# PCB_3U_BNC.net
KiCad netlist of a schematic drawn in Altium Designer
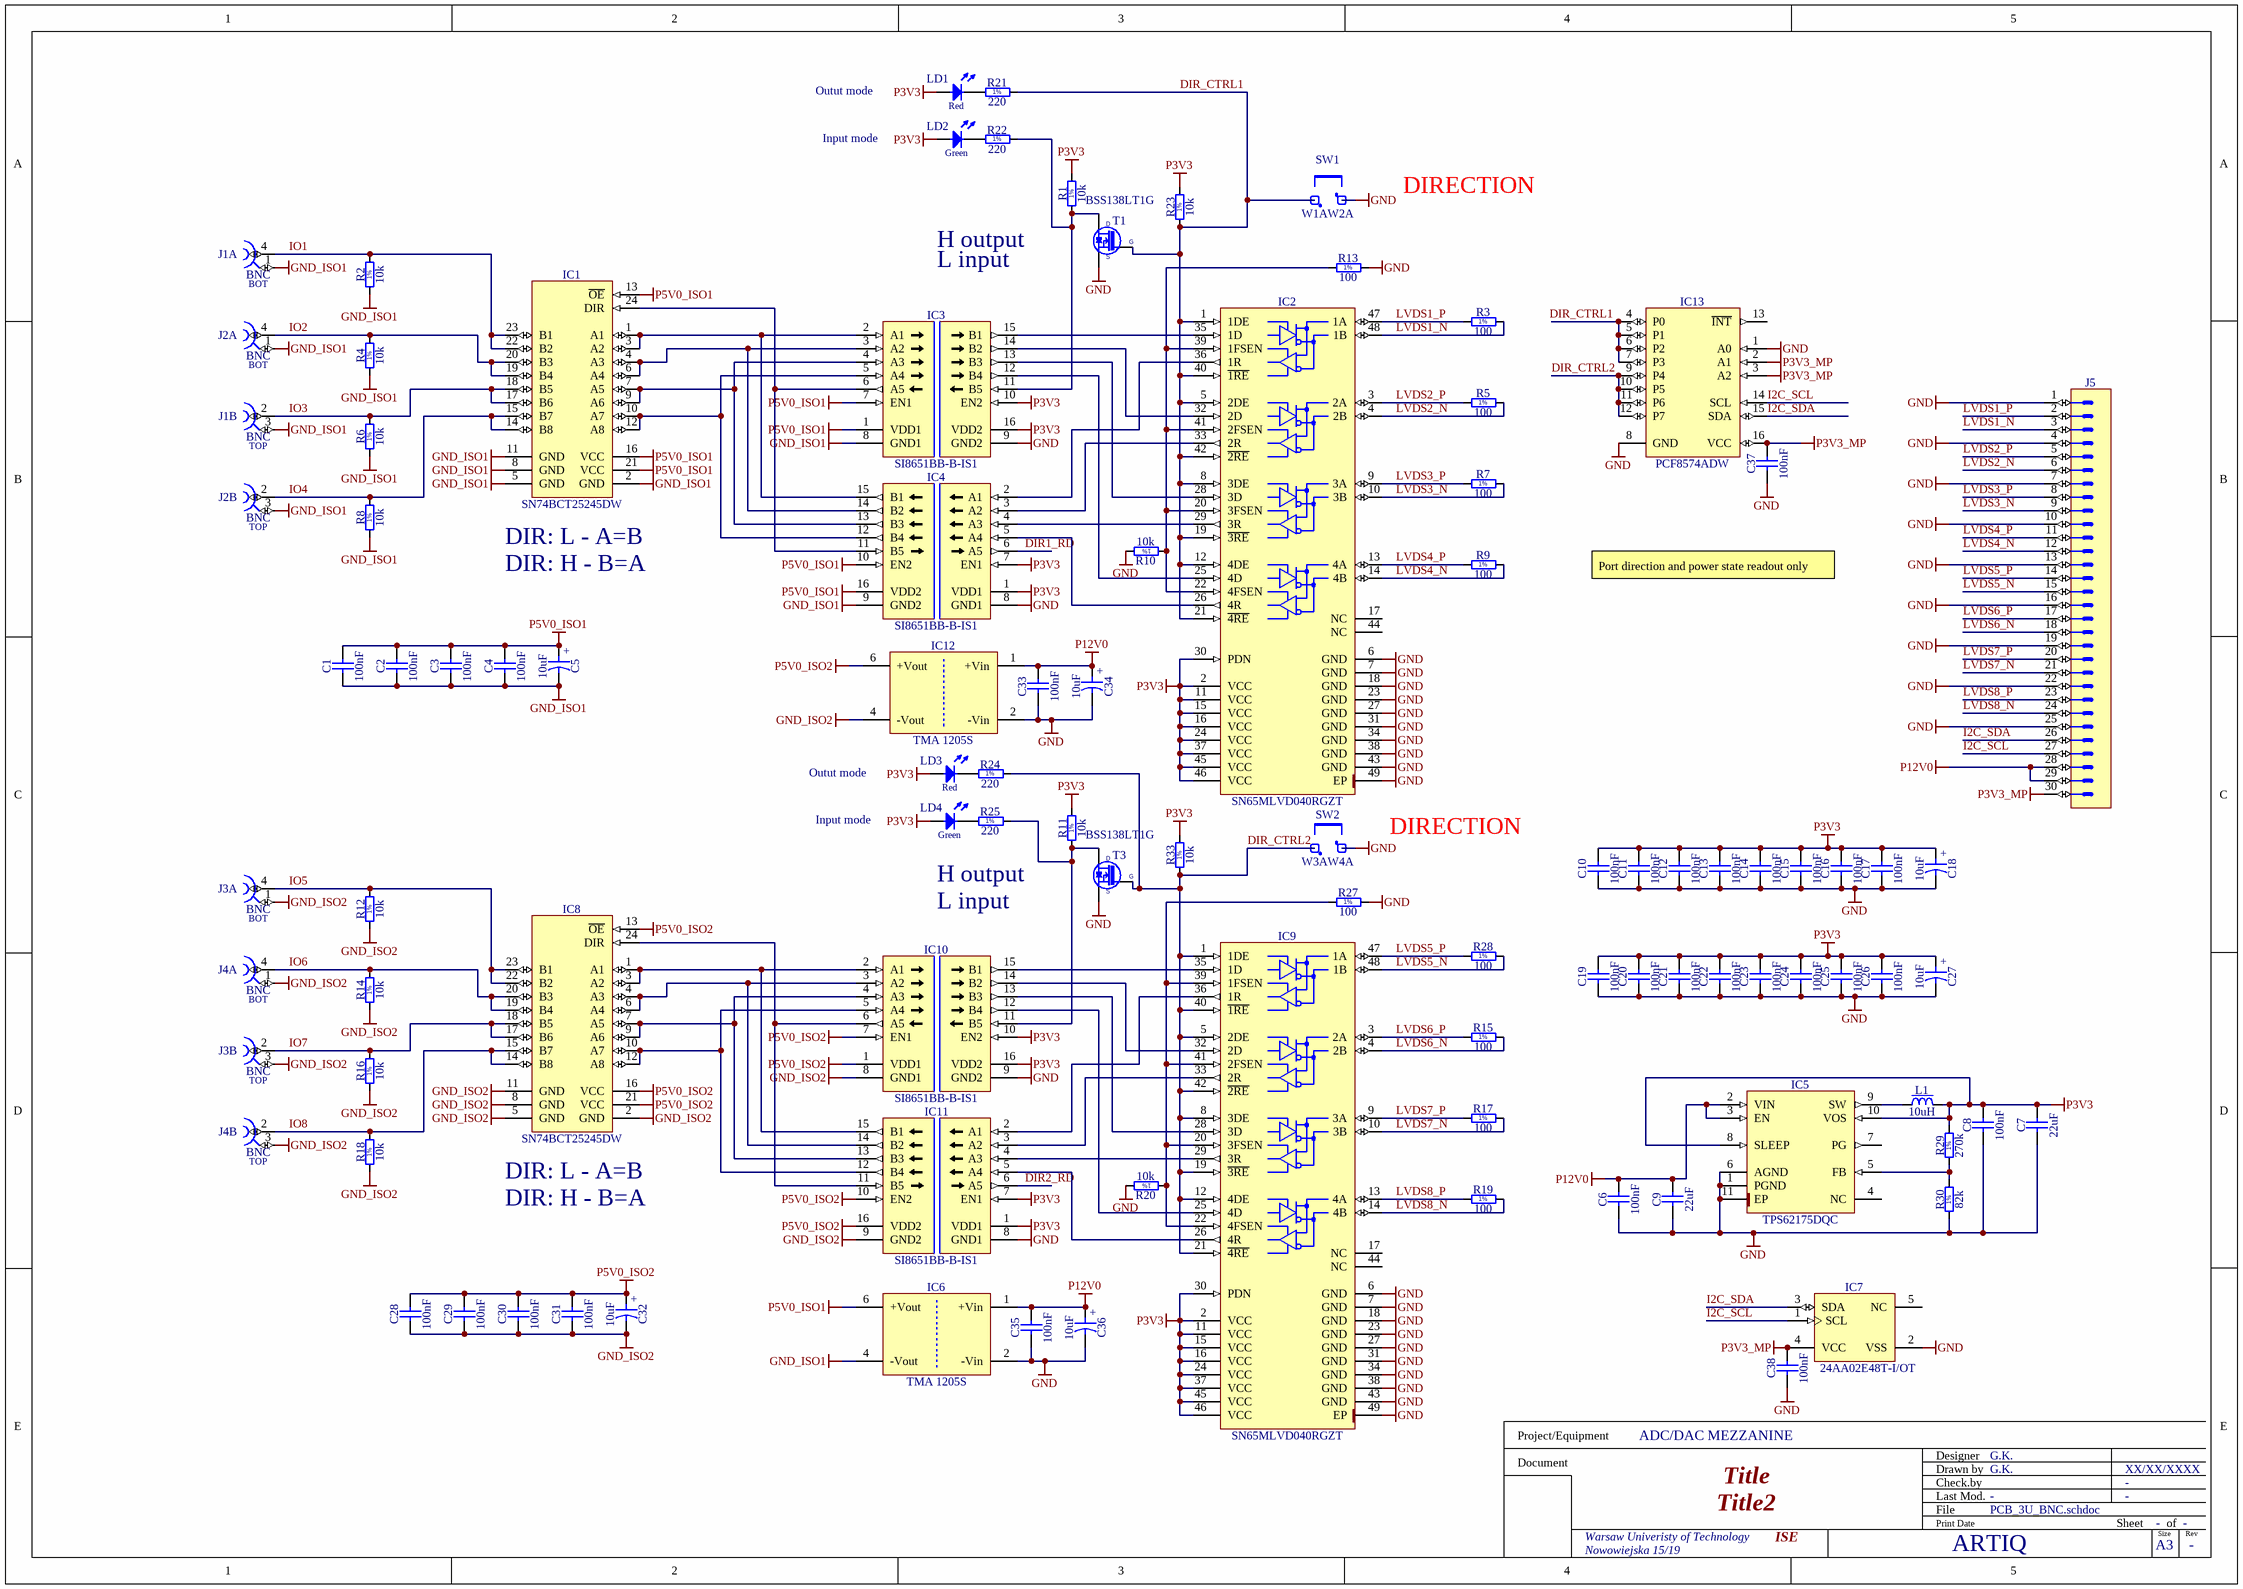
[diagram p0: PCB_3U_BNC.schdoc]

(export (version "E")
  (design (tool "Eeschema 10.0.6"))
  (components
    (comp (ref "C1")
      (value "100nF")
      (footprint "CAPC1005X55N")
      (description "Non-polarised capacitor")
      (fields
        (field (name "PART NUMBER") "CC0402_100NF_16V_10%_X5R")
        (field (name "VOLTAGE") "16V")
        (field (name "AUTHOR") "CERN DEM JLC")
      )
      (libsource (lib "Capacitors") (part "Capacitor - non polarized"))
    )
    (comp (ref "C2")
      (value "100nF")
      (footprint "CAPC1005X55N")
      (description "Non-polarised capacitor")
      (fields
        (field (name "PART NUMBER") "CC0402_100NF_16V_10%_X5R")
        (field (name "VOLTAGE") "16V")
        (field (name "AUTHOR") "CERN DEM JLC")
      )
      (libsource (lib "Capacitors") (part "Capacitor - non polarized"))
    )
    (comp (ref "C3")
      (value "100nF")
      (footprint "CAPC1005X55N")
      (description "Non-polarised capacitor")
      (fields
        (field (name "PART NUMBER") "CC0402_100NF_16V_10%_X5R")
        (field (name "VOLTAGE") "16V")
        (field (name "AUTHOR") "CERN DEM JLC")
      )
      (libsource (lib "Capacitors") (part "Capacitor - non polarized"))
    )
    (comp (ref "C4")
      (value "100nF")
      (footprint "CAPC1005X55N")
      (description "Non-polarised capacitor")
      (fields
        (field (name "PART NUMBER") "CC0402_100NF_16V_10%_X5R")
        (field (name "VOLTAGE") "16V")
        (field (name "AUTHOR") "CERN DEM JLC")
      )
      (libsource (lib "Capacitors") (part "Capacitor - non polarized"))
    )
    (comp (ref "C5")
      (value "10uF")
      (footprint "CAPAE430X540N")
      (description "Polarised capacitor")
      (fields
        (field (name "PART NUMBER") "CAE430-540_10UF_16V_20%")
        (field (name "VOLTAGE") "16V")
        (field (name "AUTHOR") "CERN DEM JLC")
      )
      (libsource (lib "Capacitors") (part "Capacitor - polarized"))
    )
    (comp (ref "C6")
      (value "100nF")
      (footprint "CAPC1005X55N")
      (description "Non-polarised capacitor")
      (fields
        (field (name "PART NUMBER") "CC0402_100NF_16V_10%_X5R")
        (field (name "VOLTAGE") "16V")
        (field (name "AUTHOR") "CERN DEM JLC")
      )
      (libsource (lib "Capacitors") (part "Capacitor - non polarized"))
    )
    (comp (ref "C7")
      (value "22uF")
      (footprint "CAPC2012X135N")
      (description "Non-polarised capacitor")
      (fields
        (field (name "PART NUMBER") "CC0805_22UF_16V_10%_X5R")
        (field (name "VOLTAGE") "16V")
        (field (name "AUTHOR") "CERN DEM JLC")
      )
      (libsource (lib "Capacitors") (part "Capacitor - non polarized"))
    )
    (comp (ref "C8")
      (value "100nF")
      (footprint "CAPC1005X55N")
      (description "Non-polarised capacitor")
      (fields
        (field (name "PART NUMBER") "CC0402_100NF_16V_10%_X5R")
        (field (name "VOLTAGE") "16V")
        (field (name "AUTHOR") "CERN DEM JLC")
      )
      (libsource (lib "Capacitors") (part "Capacitor - non polarized"))
    )
    (comp (ref "C9")
      (value "22uF")
      (footprint "CAPC2012X135N")
      (description "Non-polarised capacitor")
      (fields
        (field (name "PART NUMBER") "CC0805_22UF_16V_10%_X5R")
        (field (name "VOLTAGE") "16V")
        (field (name "AUTHOR") "CERN DEM JLC")
      )
      (libsource (lib "Capacitors") (part "Capacitor - non polarized"))
    )
    (comp (ref "C10")
      (value "100nF")
      (footprint "CAPC1005X55N")
      (description "Non-polarised capacitor")
      (fields
        (field (name "PART NUMBER") "CC0402_100NF_16V_10%_X5R")
        (field (name "VOLTAGE") "16V")
        (field (name "AUTHOR") "CERN DEM JLC")
      )
      (libsource (lib "Capacitors") (part "Capacitor - non polarized"))
    )
    (comp (ref "C11")
      (value "100nF")
      (footprint "CAPC1005X55N")
      (description "Non-polarised capacitor")
      (fields
        (field (name "PART NUMBER") "CC0402_100NF_16V_10%_X5R")
        (field (name "VOLTAGE") "16V")
        (field (name "AUTHOR") "CERN DEM JLC")
      )
      (libsource (lib "Capacitors") (part "Capacitor - non polarized"))
    )
    (comp (ref "C12")
      (value "100nF")
      (footprint "CAPC1005X55N")
      (description "Non-polarised capacitor")
      (fields
        (field (name "PART NUMBER") "CC0402_100NF_16V_10%_X5R")
        (field (name "VOLTAGE") "16V")
        (field (name "AUTHOR") "CERN DEM JLC")
      )
      (libsource (lib "Capacitors") (part "Capacitor - non polarized"))
    )
    (comp (ref "C13")
      (value "100nF")
      (footprint "CAPC1005X55N")
      (description "Non-polarised capacitor")
      (fields
        (field (name "PART NUMBER") "CC0402_100NF_16V_10%_X5R")
        (field (name "VOLTAGE") "16V")
        (field (name "AUTHOR") "CERN DEM JLC")
      )
      (libsource (lib "Capacitors") (part "Capacitor - non polarized"))
    )
    (comp (ref "C14")
      (value "100nF")
      (footprint "CAPC1005X55N")
      (description "Non-polarised capacitor")
      (fields
        (field (name "PART NUMBER") "CC0402_100NF_16V_10%_X5R")
        (field (name "VOLTAGE") "16V")
        (field (name "AUTHOR") "CERN DEM JLC")
      )
      (libsource (lib "Capacitors") (part "Capacitor - non polarized"))
    )
    (comp (ref "C15")
      (value "100nF")
      (footprint "CAPC1005X55N")
      (description "Non-polarised capacitor")
      (fields
        (field (name "PART NUMBER") "CC0402_100NF_16V_10%_X5R")
        (field (name "VOLTAGE") "16V")
        (field (name "AUTHOR") "CERN DEM JLC")
      )
      (libsource (lib "Capacitors") (part "Capacitor - non polarized"))
    )
    (comp (ref "C16")
      (value "100nF")
      (footprint "CAPC1005X55N")
      (description "Non-polarised capacitor")
      (fields
        (field (name "PART NUMBER") "CC0402_100NF_16V_10%_X5R")
        (field (name "VOLTAGE") "16V")
        (field (name "AUTHOR") "CERN DEM JLC")
      )
      (libsource (lib "Capacitors") (part "Capacitor - non polarized"))
    )
    (comp (ref "C17")
      (value "100nF")
      (footprint "CAPC1005X55N")
      (description "Non-polarised capacitor")
      (fields
        (field (name "PART NUMBER") "CC0402_100NF_16V_10%_X5R")
        (field (name "VOLTAGE") "16V")
        (field (name "AUTHOR") "CERN DEM JLC")
      )
      (libsource (lib "Capacitors") (part "Capacitor - non polarized"))
    )
    (comp (ref "C18")
      (value "10uF")
      (footprint "CAPAE430X540N")
      (description "Polarised capacitor")
      (fields
        (field (name "PART NUMBER") "CAE430-540_10UF_16V_20%")
        (field (name "VOLTAGE") "16V")
        (field (name "AUTHOR") "CERN DEM JLC")
      )
      (libsource (lib "Capacitors") (part "Capacitor - polarized"))
    )
    (comp (ref "C19")
      (value "100nF")
      (footprint "CAPC1005X55N")
      (description "Non-polarised capacitor")
      (fields
        (field (name "PART NUMBER") "CC0402_100NF_16V_10%_X5R")
        (field (name "VOLTAGE") "16V")
        (field (name "AUTHOR") "CERN DEM JLC")
      )
      (libsource (lib "Capacitors") (part "Capacitor - non polarized"))
    )
    (comp (ref "C20")
      (value "100nF")
      (footprint "CAPC1005X55N")
      (description "Non-polarised capacitor")
      (fields
        (field (name "PART NUMBER") "CC0402_100NF_16V_10%_X5R")
        (field (name "VOLTAGE") "16V")
        (field (name "AUTHOR") "CERN DEM JLC")
      )
      (libsource (lib "Capacitors") (part "Capacitor - non polarized"))
    )
    (comp (ref "C21")
      (value "100nF")
      (footprint "CAPC1005X55N")
      (description "Non-polarised capacitor")
      (fields
        (field (name "PART NUMBER") "CC0402_100NF_16V_10%_X5R")
        (field (name "VOLTAGE") "16V")
        (field (name "AUTHOR") "CERN DEM JLC")
      )
      (libsource (lib "Capacitors") (part "Capacitor - non polarized"))
    )
    (comp (ref "C22")
      (value "100nF")
      (footprint "CAPC1005X55N")
      (description "Non-polarised capacitor")
      (fields
        (field (name "PART NUMBER") "CC0402_100NF_16V_10%_X5R")
        (field (name "VOLTAGE") "16V")
        (field (name "AUTHOR") "CERN DEM JLC")
      )
      (libsource (lib "Capacitors") (part "Capacitor - non polarized"))
    )
    (comp (ref "C23")
      (value "100nF")
      (footprint "CAPC1005X55N")
      (description "Non-polarised capacitor")
      (fields
        (field (name "PART NUMBER") "CC0402_100NF_16V_10%_X5R")
        (field (name "VOLTAGE") "16V")
        (field (name "AUTHOR") "CERN DEM JLC")
      )
      (libsource (lib "Capacitors") (part "Capacitor - non polarized"))
    )
    (comp (ref "C24")
      (value "100nF")
      (footprint "CAPC1005X55N")
      (description "Non-polarised capacitor")
      (fields
        (field (name "PART NUMBER") "CC0402_100NF_16V_10%_X5R")
        (field (name "VOLTAGE") "16V")
        (field (name "AUTHOR") "CERN DEM JLC")
      )
      (libsource (lib "Capacitors") (part "Capacitor - non polarized"))
    )
    (comp (ref "C25")
      (value "100nF")
      (footprint "CAPC1005X55N")
      (description "Non-polarised capacitor")
      (fields
        (field (name "PART NUMBER") "CC0402_100NF_16V_10%_X5R")
        (field (name "VOLTAGE") "16V")
        (field (name "AUTHOR") "CERN DEM JLC")
      )
      (libsource (lib "Capacitors") (part "Capacitor - non polarized"))
    )
    (comp (ref "C26")
      (value "100nF")
      (footprint "CAPC1005X55N")
      (description "Non-polarised capacitor")
      (fields
        (field (name "PART NUMBER") "CC0402_100NF_16V_10%_X5R")
        (field (name "VOLTAGE") "16V")
        (field (name "AUTHOR") "CERN DEM JLC")
      )
      (libsource (lib "Capacitors") (part "Capacitor - non polarized"))
    )
    (comp (ref "C27")
      (value "10uF")
      (footprint "CAPAE430X540N")
      (description "Polarised capacitor")
      (fields
        (field (name "PART NUMBER") "CAE430-540_10UF_16V_20%")
        (field (name "VOLTAGE") "16V")
        (field (name "AUTHOR") "CERN DEM JLC")
      )
      (libsource (lib "Capacitors") (part "Capacitor - polarized"))
    )
    (comp (ref "C28")
      (value "100nF")
      (footprint "CAPC1005X55N")
      (description "Non-polarised capacitor")
      (fields
        (field (name "PART NUMBER") "CC0402_100NF_16V_10%_X5R")
        (field (name "VOLTAGE") "16V")
        (field (name "AUTHOR") "CERN DEM JLC")
      )
      (libsource (lib "Capacitors") (part "Capacitor - non polarized"))
    )
    (comp (ref "C29")
      (value "100nF")
      (footprint "CAPC1005X55N")
      (description "Non-polarised capacitor")
      (fields
        (field (name "PART NUMBER") "CC0402_100NF_16V_10%_X5R")
        (field (name "VOLTAGE") "16V")
        (field (name "AUTHOR") "CERN DEM JLC")
      )
      (libsource (lib "Capacitors") (part "Capacitor - non polarized"))
    )
    (comp (ref "C30")
      (value "100nF")
      (footprint "CAPC1005X55N")
      (description "Non-polarised capacitor")
      (fields
        (field (name "PART NUMBER") "CC0402_100NF_16V_10%_X5R")
        (field (name "VOLTAGE") "16V")
        (field (name "AUTHOR") "CERN DEM JLC")
      )
      (libsource (lib "Capacitors") (part "Capacitor - non polarized"))
    )
    (comp (ref "C31")
      (value "100nF")
      (footprint "CAPC1005X55N")
      (description "Non-polarised capacitor")
      (fields
        (field (name "PART NUMBER") "CC0402_100NF_16V_10%_X5R")
        (field (name "VOLTAGE") "16V")
        (field (name "AUTHOR") "CERN DEM JLC")
      )
      (libsource (lib "Capacitors") (part "Capacitor - non polarized"))
    )
    (comp (ref "C32")
      (value "10uF")
      (footprint "CAPAE430X540N")
      (description "Polarised capacitor")
      (fields
        (field (name "PART NUMBER") "CAE430-540_10UF_16V_20%")
        (field (name "VOLTAGE") "16V")
        (field (name "AUTHOR") "CERN DEM JLC")
      )
      (libsource (lib "Capacitors") (part "Capacitor - polarized"))
    )
    (comp (ref "C33")
      (value "100nF")
      (footprint "CAPC1005X55N")
      (description "Non-polarised capacitor")
      (fields
        (field (name "PART NUMBER") "CC0402_100NF_16V_10%_X5R")
        (field (name "VOLTAGE") "16V")
        (field (name "AUTHOR") "CERN DEM JLC")
      )
      (libsource (lib "Capacitors") (part "Capacitor - non polarized"))
    )
    (comp (ref "C34")
      (value "10uF")
      (footprint "CAPAE430X540N")
      (description "Polarised capacitor")
      (fields
        (field (name "PART NUMBER") "CAE430-540_10UF_16V_20%")
        (field (name "VOLTAGE") "16V")
        (field (name "AUTHOR") "CERN DEM JLC")
      )
      (libsource (lib "Capacitors") (part "Capacitor - polarized"))
    )
    (comp (ref "C35")
      (value "100nF")
      (footprint "CAPC1005X55N")
      (description "Non-polarised capacitor")
      (fields
        (field (name "PART NUMBER") "CC0402_100NF_16V_10%_X5R")
        (field (name "VOLTAGE") "16V")
        (field (name "AUTHOR") "CERN DEM JLC")
      )
      (libsource (lib "Capacitors") (part "Capacitor - non polarized"))
    )
    (comp (ref "C36")
      (value "10uF")
      (footprint "CAPAE430X540N")
      (description "Polarised capacitor")
      (fields
        (field (name "PART NUMBER") "CAE430-540_10UF_16V_20%")
        (field (name "VOLTAGE") "16V")
        (field (name "AUTHOR") "CERN DEM JLC")
      )
      (libsource (lib "Capacitors") (part "Capacitor - polarized"))
    )
    (comp (ref "C37")
      (value "100nF")
      (footprint "CAPC1005X55N")
      (description "Non-polarised capacitor")
      (fields
        (field (name "PART NUMBER") "CC0402_100NF_16V_10%_X5R")
        (field (name "VOLTAGE") "16V")
        (field (name "AUTHOR") "CERN DEM JLC")
      )
      (libsource (lib "Capacitors") (part "Capacitor - non polarized"))
    )
    (comp (ref "C38")
      (value "100nF")
      (footprint "CAPC1005X55N")
      (description "Non-polarised capacitor")
      (fields
        (field (name "PART NUMBER") "CC0402_100NF_16V_10%_X5R")
        (field (name "VOLTAGE") "16V")
        (field (name "AUTHOR") "CERN DEM JLC")
      )
      (libsource (lib "Capacitors") (part "Capacitor - non polarized"))
    )
    (comp (ref "IC1")
      (value "SN74BCT25245DW")
      (footprint "SOIC127P1030X265-24N")
      (description "25 Ohms Octal Bus Transceiver With 3-State Outputs")
      (fields (field (name "MANUFACTURER") "TEXAS INSTRUMENTS") (field (name "AUTHOR") "CERN DEM JLC"))
      (libsource (lib "ICs And Semiconductors") (part "7425245"))
    )
    (comp (ref "IC2")
      (value "SN65MLVD040RGZT")
      (footprint "QFN50P700X700X100-49N-S420")
      (description "4-Channel Half-Duplex M-LVDS Line Transceiver")
      (fields (field (name "MANUFACTURER") "TEXAS INSTRUMENTS") (field (name "AUTHOR") "CERN DEM JLC"))
      (libsource (lib "ICs And Semiconductors") (part "SN65MLVD040"))
    )
    (comp (ref "IC3")
      (value "SI8651BB-B-IS1")
      (footprint "SOIC127P600X175-16N")
      (description "Low Power Five-Channel Digital Isolator")
      (fields (field (name "MANUFACTURER") "SILICON LABS") (field (name "AUTHOR") "CERN DEM JLC"))
      (libsource (lib "") (part "Si8651_1"))
    )
    (comp (ref "IC4")
      (value "SI8651BB-B-IS1")
      (footprint "SOIC127P600X175-16N")
      (description "Low Power Five-Channel Digital Isolator")
      (fields (field (name "MANUFACTURER") "SILICON LABS") (field (name "AUTHOR") "CERN DEM JLC"))
      (libsource (lib "ICs And Semiconductors") (part "Si8651"))
    )
    (comp (ref "IC5")
      (value "TPS62175DQC")
      (footprint "SON50P200X300X80-11N-R94X250")
      (description "4.75-28VDC to 1-6VDC, 500mA Step-Down Converter With Sleep Mode")
      (fields (field (name "MANUFACTURER") "TEXAS INSTRUMENTS") (field (name "AUTHOR") "CERN DEM JMW"))
      (libsource (lib "ICs And Semiconductors") (part "TPS62175"))
    )
    (comp (ref "IC6")
      (value "TMA 1205S")
      (footprint "DCDC_TRACO_TMA")
      (description "1 W Watt, 10.8-13.2VDCVin, 5 V@0.2 A")
      (fields (field (name "MANUFACTURER") "TRACO POWER") (field (name "AUTHOR") "GK"))
      (libsource (lib "LIBRARY_SCH") (part "DC/DC_TRACO_TMA1205S"))
    )
    (comp (ref "IC7")
      (value "24AA02E48T-I/OT")
      (footprint "SOT95P280X145-5N")
      (description "1.7V-5.5V, 2K I2C Serial EEPROM With EUI-48 Node Identity")
      (fields (field (name "MANUFACTURER") "MICROCHIP TECHNOLOGY") (field (name "AUTHOR") "CERN DEM MR"))
      (libsource (lib "ICs And Semiconductors") (part "24AA02E48T-I/OT"))
    )
    (comp (ref "IC8")
      (value "SN74BCT25245DW")
      (footprint "SOIC127P1030X265-24N")
      (description "25 Ohms Octal Bus Transceiver With 3-State Outputs")
      (fields (field (name "MANUFACTURER") "TEXAS INSTRUMENTS") (field (name "AUTHOR") "CERN DEM JLC"))
      (libsource (lib "ICs And Semiconductors") (part "7425245"))
    )
    (comp (ref "IC9")
      (value "SN65MLVD040RGZT")
      (footprint "QFN50P700X700X100-49N-S420")
      (description "4-Channel Half-Duplex M-LVDS Line Transceiver")
      (fields (field (name "MANUFACTURER") "TEXAS INSTRUMENTS") (field (name "AUTHOR") "CERN DEM JLC"))
      (libsource (lib "ICs And Semiconductors") (part "SN65MLVD040"))
    )
    (comp (ref "IC10")
      (value "SI8651BB-B-IS1")
      (footprint "SOIC127P600X175-16N")
      (description "Low Power Five-Channel Digital Isolator")
      (fields (field (name "MANUFACTURER") "SILICON LABS") (field (name "AUTHOR") "CERN DEM JLC"))
      (libsource (lib "") (part "Si8651_1"))
    )
    (comp (ref "IC11")
      (value "SI8651BB-B-IS1")
      (footprint "SOIC127P600X175-16N")
      (description "Low Power Five-Channel Digital Isolator")
      (fields (field (name "MANUFACTURER") "SILICON LABS") (field (name "AUTHOR") "CERN DEM JLC"))
      (libsource (lib "ICs And Semiconductors") (part "Si8651"))
    )
    (comp (ref "IC12")
      (value "TMA 1205S")
      (footprint "DCDC_TRACO_TMA")
      (description "1 W Watt, 10.8-13.2VDCVin, 5 V@0.2 A")
      (fields (field (name "MANUFACTURER") "TRACO POWER") (field (name "AUTHOR") "GK"))
      (libsource (lib "LIBRARY_SCH") (part "DC/DC_TRACO_TMA1205S"))
    )
    (comp (ref "IC13")
      (value "PCF8574ADW")
      (footprint "SOIC127P1030X265-16N")
      (description "Remote 8-bit I/O Expander For I2C Bus")
      (fields (field (name "MANUFACTURER") "TEXAS INSTRUMENTS") (field (name "AUTHOR") "CERN DEM JLC"))
      (libsource (lib "ICs And Semiconductors") (part "PCF8574ADW"))
    )
    (comp (ref "J1")
      (value "BNC")
      (footprint "BOMAR_364A2595")
      (description "Dual Right Angle 50 Ohm BNC Jack, White Valox Case")
      (fields
        (field (name "PART NUMBER") "BOMAR_364A2595")
        (field (name "MANUFACTURER") "BOMAR INTERCONNECT")
        (field (name "AUTHOR") "CERN DEM JLC")
      )
      (libsource (lib "Connectors") (part "BOMAR_364A2595"))
    )
    (comp (ref "J2")
      (value "BNC")
      (footprint "BOMAR_364A2595")
      (description "Dual Right Angle 50 Ohm BNC Jack, White Valox Case")
      (fields
        (field (name "PART NUMBER") "BOMAR_364A2595")
        (field (name "MANUFACTURER") "BOMAR INTERCONNECT")
        (field (name "AUTHOR") "CERN DEM JLC")
      )
      (libsource (lib "Connectors") (part "BOMAR_364A2595"))
    )
    (comp (ref "J3")
      (value "BNC")
      (footprint "BOMAR_364A2595")
      (description "Dual Right Angle 50 Ohm BNC Jack, White Valox Case")
      (fields
        (field (name "PART NUMBER") "BOMAR_364A2595")
        (field (name "MANUFACTURER") "BOMAR INTERCONNECT")
        (field (name "AUTHOR") "CERN DEM JLC")
      )
      (libsource (lib "Connectors") (part "BOMAR_364A2595"))
    )
    (comp (ref "J4")
      (value "BNC")
      (footprint "BOMAR_364A2595")
      (description "Dual Right Angle 50 Ohm BNC Jack, White Valox Case")
      (fields
        (field (name "PART NUMBER") "BOMAR_364A2595")
        (field (name "MANUFACTURER") "BOMAR INTERCONNECT")
        (field (name "AUTHOR") "CERN DEM JLC")
      )
      (libsource (lib "Connectors") (part "BOMAR_364A2595"))
    )
    (comp (ref "J5")
      (value "~")
      (footprint "3M_N2530-6002RB")
      (description "Connector 30 Male")
      (fields
        (field (name "PART NUMBER") "3M_N2530-6002RB")
        (field (name "MANUFACTURER") "3M")
        (field (name "AUTHOR") "CERN DEM JLC")
      )
      (libsource (lib "Connectors") (part "Connector 30 Male"))
    )
    (comp (ref "L1")
      (value "10uH")
      (footprint "IND_MURATA-PS_8400")
      (description "Inductor With Core")
      (fields
        (field (name "PART NUMBER") "IND_10UH_10%_MURATA-PS_8400")
        (field (name "POWER") "950mA")
        (field (name "AUTHOR") "CERN DEM JLC")
      )
      (libsource (lib "Inductors & Transformers") (part "Inductor With Magnetic core"))
    )
    (comp (ref "LD1")
      (value "Red")
      (footprint "LED_AVAGO_HSMC-C120")
      (description "LED Red 1C 2A")
      (fields
        (field (name "PART NUMBER") "LED_AVAGO_HSMC-C120")
        (field (name "MANUFACTURER") "AVAGO TECHNOLOGIES")
        (field (name "AUTHOR") "CERN DEM JMW")
      )
      (libsource (lib "ICs And Semiconductors") (part "LED Red 1C 2A"))
    )
    (comp (ref "LD2")
      (value "Green")
      (footprint "LED_AVAGO_HSME-C120")
      (description "LED Green 1C 2A")
      (fields
        (field (name "PART NUMBER") "LED_AVAGO_HSME-C120")
        (field (name "MANUFACTURER") "AVAGO TECHNOLOGIES")
        (field (name "AUTHOR") "CERN DEM JMW")
      )
      (libsource (lib "ICs And Semiconductors") (part "LED Green 1C 2A"))
    )
    (comp (ref "LD3")
      (value "Red")
      (footprint "LED_AVAGO_HSMC-C120")
      (description "LED Red 1C 2A")
      (fields
        (field (name "PART NUMBER") "LED_AVAGO_HSMC-C120")
        (field (name "MANUFACTURER") "AVAGO TECHNOLOGIES")
        (field (name "AUTHOR") "CERN DEM JMW")
      )
      (libsource (lib "ICs And Semiconductors") (part "LED Red 1C 2A"))
    )
    (comp (ref "LD4")
      (value "Green")
      (footprint "LED_AVAGO_HSME-C120")
      (description "LED Green 1C 2A")
      (fields
        (field (name "PART NUMBER") "LED_AVAGO_HSME-C120")
        (field (name "MANUFACTURER") "AVAGO TECHNOLOGIES")
        (field (name "AUTHOR") "CERN DEM JMW")
      )
      (libsource (lib "ICs And Semiconductors") (part "LED Green 1C 2A"))
    )
    (comp (ref "R1")
      (value "10k")
      (footprint "RESC1005X40N")
      (description "Resistor - 1%")
      (fields
        (field (name "PART NUMBER") "R0402_10K_1%_0.0625W_100PPM")
        (field (name "POWER") "0.0625W")
        (field (name "AUTHOR") "CERN DEM JLC")
      )
      (libsource (lib "Resistors") (part "Resistor - 1%"))
    )
    (comp (ref "R2")
      (value "10k")
      (footprint "RESC1005X40N")
      (description "Resistor - 1%")
      (fields
        (field (name "PART NUMBER") "R0402_10K_1%_0.0625W_100PPM")
        (field (name "POWER") "0.0625W")
        (field (name "AUTHOR") "CERN DEM JLC")
      )
      (libsource (lib "Resistors") (part "Resistor - 1%"))
    )
    (comp (ref "R3")
      (value "100")
      (footprint "RESC1005X40N")
      (description "Resistor - 1%")
      (fields
        (field (name "PART NUMBER") "R0402_100R_1%_0.1W_100PPM")
        (field (name "POWER") "0.1W")
        (field (name "AUTHOR") "CERN DEM JLC")
      )
      (libsource (lib "Resistors") (part "Resistor - 1%"))
    )
    (comp (ref "R4")
      (value "10k")
      (footprint "RESC1005X40N")
      (description "Resistor - 1%")
      (fields
        (field (name "PART NUMBER") "R0402_10K_1%_0.0625W_100PPM")
        (field (name "POWER") "0.0625W")
        (field (name "AUTHOR") "CERN DEM JLC")
      )
      (libsource (lib "Resistors") (part "Resistor - 1%"))
    )
    (comp (ref "R5")
      (value "100")
      (footprint "RESC1005X40N")
      (description "Resistor - 1%")
      (fields
        (field (name "PART NUMBER") "R0402_100R_1%_0.1W_100PPM")
        (field (name "POWER") "0.1W")
        (field (name "AUTHOR") "CERN DEM JLC")
      )
      (libsource (lib "Resistors") (part "Resistor - 1%"))
    )
    (comp (ref "R6")
      (value "10k")
      (footprint "RESC1005X40N")
      (description "Resistor - 1%")
      (fields
        (field (name "PART NUMBER") "R0402_10K_1%_0.0625W_100PPM")
        (field (name "POWER") "0.0625W")
        (field (name "AUTHOR") "CERN DEM JLC")
      )
      (libsource (lib "Resistors") (part "Resistor - 1%"))
    )
    (comp (ref "R7")
      (value "100")
      (footprint "RESC1005X40N")
      (description "Resistor - 1%")
      (fields
        (field (name "PART NUMBER") "R0402_100R_1%_0.1W_100PPM")
        (field (name "POWER") "0.1W")
        (field (name "AUTHOR") "CERN DEM JLC")
      )
      (libsource (lib "Resistors") (part "Resistor - 1%"))
    )
    (comp (ref "R8")
      (value "10k")
      (footprint "RESC1005X40N")
      (description "Resistor - 1%")
      (fields
        (field (name "PART NUMBER") "R0402_10K_1%_0.0625W_100PPM")
        (field (name "POWER") "0.0625W")
        (field (name "AUTHOR") "CERN DEM JLC")
      )
      (libsource (lib "Resistors") (part "Resistor - 1%"))
    )
    (comp (ref "R9")
      (value "100")
      (footprint "RESC1005X40N")
      (description "Resistor - 1%")
      (fields
        (field (name "PART NUMBER") "R0402_100R_1%_0.1W_100PPM")
        (field (name "POWER") "0.1W")
        (field (name "AUTHOR") "CERN DEM JLC")
      )
      (libsource (lib "Resistors") (part "Resistor - 1%"))
    )
    (comp (ref "R10")
      (value "10k")
      (footprint "RESC1005X40N")
      (description "Resistor - 1%")
      (fields
        (field (name "PART NUMBER") "R0402_10K_1%_0.0625W_100PPM")
        (field (name "POWER") "0.0625W")
        (field (name "AUTHOR") "CERN DEM JLC")
      )
      (libsource (lib "Resistors") (part "Resistor - 1%"))
    )
    (comp (ref "R11")
      (value "10k")
      (footprint "RESC1005X40N")
      (description "Resistor - 1%")
      (fields
        (field (name "PART NUMBER") "R0402_10K_1%_0.0625W_100PPM")
        (field (name "POWER") "0.0625W")
        (field (name "AUTHOR") "CERN DEM JLC")
      )
      (libsource (lib "Resistors") (part "Resistor - 1%"))
    )
    (comp (ref "R12")
      (value "10k")
      (footprint "RESC1005X40N")
      (description "Resistor - 1%")
      (fields
        (field (name "PART NUMBER") "R0402_10K_1%_0.0625W_100PPM")
        (field (name "POWER") "0.0625W")
        (field (name "AUTHOR") "CERN DEM JLC")
      )
      (libsource (lib "Resistors") (part "Resistor - 1%"))
    )
    (comp (ref "R13")
      (value "100")
      (footprint "RESC1005X40N")
      (description "Resistor - 1%")
      (fields
        (field (name "PART NUMBER") "R0402_100R_1%_0.1W_100PPM")
        (field (name "POWER") "0.1W")
        (field (name "AUTHOR") "CERN DEM JLC")
      )
      (libsource (lib "Resistors") (part "Resistor - 1%"))
    )
    (comp (ref "R14")
      (value "10k")
      (footprint "RESC1005X40N")
      (description "Resistor - 1%")
      (fields
        (field (name "PART NUMBER") "R0402_10K_1%_0.0625W_100PPM")
        (field (name "POWER") "0.0625W")
        (field (name "AUTHOR") "CERN DEM JLC")
      )
      (libsource (lib "Resistors") (part "Resistor - 1%"))
    )
    (comp (ref "R15")
      (value "100")
      (footprint "RESC1005X40N")
      (description "Resistor - 1%")
      (fields
        (field (name "PART NUMBER") "R0402_100R_1%_0.1W_100PPM")
        (field (name "POWER") "0.1W")
        (field (name "AUTHOR") "CERN DEM JLC")
      )
      (libsource (lib "Resistors") (part "Resistor - 1%"))
    )
    (comp (ref "R16")
      (value "10k")
      (footprint "RESC1005X40N")
      (description "Resistor - 1%")
      (fields
        (field (name "PART NUMBER") "R0402_10K_1%_0.0625W_100PPM")
        (field (name "POWER") "0.0625W")
        (field (name "AUTHOR") "CERN DEM JLC")
      )
      (libsource (lib "Resistors") (part "Resistor - 1%"))
    )
    (comp (ref "R17")
      (value "100")
      (footprint "RESC1005X40N")
      (description "Resistor - 1%")
      (fields
        (field (name "PART NUMBER") "R0402_100R_1%_0.1W_100PPM")
        (field (name "POWER") "0.1W")
        (field (name "AUTHOR") "CERN DEM JLC")
      )
      (libsource (lib "Resistors") (part "Resistor - 1%"))
    )
    (comp (ref "R18")
      (value "10k")
      (footprint "RESC1005X40N")
      (description "Resistor - 1%")
      (fields
        (field (name "PART NUMBER") "R0402_10K_1%_0.0625W_100PPM")
        (field (name "POWER") "0.0625W")
        (field (name "AUTHOR") "CERN DEM JLC")
      )
      (libsource (lib "Resistors") (part "Resistor - 1%"))
    )
    (comp (ref "R19")
      (value "100")
      (footprint "RESC1005X40N")
      (description "Resistor - 1%")
      (fields
        (field (name "PART NUMBER") "R0402_100R_1%_0.1W_100PPM")
        (field (name "POWER") "0.1W")
        (field (name "AUTHOR") "CERN DEM JLC")
      )
      (libsource (lib "Resistors") (part "Resistor - 1%"))
    )
    (comp (ref "R20")
      (value "10k")
      (footprint "RESC1005X40N")
      (description "Resistor - 1%")
      (fields
        (field (name "PART NUMBER") "R0402_10K_1%_0.0625W_100PPM")
        (field (name "POWER") "0.0625W")
        (field (name "AUTHOR") "CERN DEM JLC")
      )
      (libsource (lib "Resistors") (part "Resistor - 1%"))
    )
    (comp (ref "R21")
      (value "220")
      (footprint "RESC1608X55N")
      (description "Resistor - 1%")
      (fields
        (field (name "PART NUMBER") "R0603_220R_1%_0.1W_100PPM")
        (field (name "POWER") "0.1W")
        (field (name "AUTHOR") "CERN DEM JLC")
      )
      (libsource (lib "Resistors") (part "Resistor - 1%"))
    )
    (comp (ref "R22")
      (value "220")
      (footprint "RESC1608X55N")
      (description "Resistor - 1%")
      (fields
        (field (name "PART NUMBER") "R0603_220R_1%_0.1W_100PPM")
        (field (name "POWER") "0.1W")
        (field (name "AUTHOR") "CERN DEM JLC")
      )
      (libsource (lib "Resistors") (part "Resistor - 1%"))
    )
    (comp (ref "R23")
      (value "10k")
      (footprint "RESC1005X40N")
      (description "Resistor - 1%")
      (fields
        (field (name "PART NUMBER") "R0402_10K_1%_0.0625W_100PPM")
        (field (name "POWER") "0.0625W")
        (field (name "AUTHOR") "CERN DEM JLC")
      )
      (libsource (lib "Resistors") (part "Resistor - 1%"))
    )
    (comp (ref "R24")
      (value "220")
      (footprint "RESC1608X55N")
      (description "Resistor - 1%")
      (fields
        (field (name "PART NUMBER") "R0603_220R_1%_0.1W_100PPM")
        (field (name "POWER") "0.1W")
        (field (name "AUTHOR") "CERN DEM JLC")
      )
      (libsource (lib "Resistors") (part "Resistor - 1%"))
    )
    (comp (ref "R25")
      (value "220")
      (footprint "RESC1608X55N")
      (description "Resistor - 1%")
      (fields
        (field (name "PART NUMBER") "R0603_220R_1%_0.1W_100PPM")
        (field (name "POWER") "0.1W")
        (field (name "AUTHOR") "CERN DEM JLC")
      )
      (libsource (lib "Resistors") (part "Resistor - 1%"))
    )
    (comp (ref "R27")
      (value "100")
      (footprint "RESC1005X40N")
      (description "Resistor - 1%")
      (fields
        (field (name "PART NUMBER") "R0402_100R_1%_0.1W_100PPM")
        (field (name "POWER") "0.1W")
        (field (name "AUTHOR") "CERN DEM JLC")
      )
      (libsource (lib "Resistors") (part "Resistor - 1%"))
    )
    (comp (ref "R28")
      (value "100")
      (footprint "RESC1005X40N")
      (description "Resistor - 1%")
      (fields
        (field (name "PART NUMBER") "R0402_100R_1%_0.1W_100PPM")
        (field (name "POWER") "0.1W")
        (field (name "AUTHOR") "CERN DEM JLC")
      )
      (libsource (lib "Resistors") (part "Resistor - 1%"))
    )
    (comp (ref "R29")
      (value "270k")
      (footprint "RESC1608X55N")
      (description "Resistor - 1%")
      (fields
        (field (name "PART NUMBER") "R0603_270K_1%_0.1W_100PPM")
        (field (name "POWER") "0.1W")
        (field (name "AUTHOR") "CERN DEM JLC")
      )
      (libsource (lib "Resistors") (part "Resistor - 1%"))
    )
    (comp (ref "R30")
      (value "82k")
      (footprint "RESC1608X55N")
      (description "Resistor - 1%")
      (fields
        (field (name "PART NUMBER") "R0603_82K_1%_0.1W_100PPM")
        (field (name "POWER") "0.1W")
        (field (name "AUTHOR") "CERN DEM JLC")
      )
      (libsource (lib "Resistors") (part "Resistor - 1%"))
    )
    (comp (ref "R33")
      (value "10k")
      (footprint "RESC1005X40N")
      (description "Resistor - 1%")
      (fields
        (field (name "PART NUMBER") "R0402_10K_1%_0.0625W_100PPM")
        (field (name "POWER") "0.0625W")
        (field (name "AUTHOR") "CERN DEM JLC")
      )
      (libsource (lib "Resistors") (part "Resistor - 1%"))
    )
    (comp (ref "SW1")
      (value "Jumper Type1")
      (footprint "JUMPER_BLACK_INSULATED_2.54MM")
      (description "Jumper 1 Pin")
      (fields
        (field (name "PART NUMBER") "COMATEL_313.1730.0.00.40.0")
        (field (name "MANUFACTURER") "KONTEK COMATEL")
        (field (name "AUTHOR") "CERN DEM JLC")
      )
      (libsource (lib "Connectors") (part "Jumper Type1"))
    )
    (comp (ref "SW2")
      (value "Jumper Type1")
      (footprint "JUMPER_BLACK_INSULATED_2.54MM")
      (description "Jumper 1 Pin")
      (fields
        (field (name "PART NUMBER") "COMATEL_313.1730.0.00.40.0")
        (field (name "MANUFACTURER") "KONTEK COMATEL")
        (field (name "AUTHOR") "CERN DEM JLC")
      )
      (libsource (lib "Connectors") (part "Jumper Type1"))
    )
    (comp (ref "T1")
      (value "BSS138LT1G")
      (footprint "SOT95P240X110-3N")
      (description "N-CHANNEL MOSFET WITH DIODE")
      (fields (field (name "MANUFACTURER") "ON SEMICONDUCTOR") (field (name "AUTHOR") "CERN DEM JLC"))
      (libsource (lib "ICs And Semiconductors") (part "N-MOSFET-D 1G 2S 3D"))
    )
    (comp (ref "T3")
      (value "BSS138LT1G")
      (footprint "SOT95P240X110-3N")
      (description "N-CHANNEL MOSFET WITH DIODE")
      (fields (field (name "MANUFACTURER") "ON SEMICONDUCTOR") (field (name "AUTHOR") "CERN DEM JLC"))
      (libsource (lib "ICs And Semiconductors") (part "N-MOSFET-D 1G 2S 3D"))
    )
    (comp (ref "W1")
      (value "Test Point")
      (footprint "COMATEL_385.0358.1.02.400")
      (description "2 Mini Wire-Wrap Contact Strip Header")
      (fields
        (field (name "PART NUMBER") "COMATEL_385.0358.1.02.400")
        (field (name "MANUFACTURER") "KONTEK COMATEL")
        (field (name "AUTHOR") "CERN DEM JLC")
      )
      (libsource (lib "Connectors") (part "Wire-Wrap Contact x2"))
    )
    (comp (ref "W2")
      (value "Test Point")
      (footprint "COMATEL_385.0358.1.02.400")
      (description "2 Mini Wire-Wrap Contact Strip Header")
      (fields
        (field (name "PART NUMBER") "COMATEL_385.0358.1.02.400")
        (field (name "MANUFACTURER") "KONTEK COMATEL")
        (field (name "AUTHOR") "CERN DEM JLC")
      )
      (libsource (lib "Connectors") (part "Wire-Wrap Contact x2"))
    )
    (comp (ref "W3")
      (value "Test Point")
      (footprint "COMATEL_385.0358.1.02.400")
      (description "2 Mini Wire-Wrap Contact Strip Header")
      (fields
        (field (name "PART NUMBER") "COMATEL_385.0358.1.02.400")
        (field (name "MANUFACTURER") "KONTEK COMATEL")
        (field (name "AUTHOR") "CERN DEM JLC")
      )
      (libsource (lib "Connectors") (part "Wire-Wrap Contact x2"))
    )
    (comp (ref "W4")
      (value "Test Point")
      (footprint "COMATEL_385.0358.1.02.400")
      (description "2 Mini Wire-Wrap Contact Strip Header")
      (fields
        (field (name "PART NUMBER") "COMATEL_385.0358.1.02.400")
        (field (name "MANUFACTURER") "KONTEK COMATEL")
        (field (name "AUTHOR") "CERN DEM JLC")
      )
      (libsource (lib "Connectors") (part "Wire-Wrap Contact x2"))
    )
  )
  (nets
    (net (code "1") (name "/DIR1_RD") (class "Default")
      (node (ref "IC4") (pin "6") (pinfunction "A5_6") (pintype "output"))
    )
    (net (code "2") (name "/DIR2_RD") (class "Default")
      (node (ref "IC11") (pin "6") (pinfunction "A5_6") (pintype "output"))
    )
    (net (code "3") (name "/DIR_CTRL1") (class "Default")
      (node (ref "IC2") (pin "1") (pinfunction "1DE_1") (pintype "input"))
      (node (ref "IC2") (pin "12") (pinfunction "4DE_12") (pintype "input"))
      (node (ref "IC2") (pin "19") (pinfunction "~{3RE}_19") (pintype "input"))
      (node (ref "IC2") (pin "21") (pinfunction "~{4RE}_21") (pintype "input"))
      (node (ref "IC2") (pin "40") (pinfunction "~{1RE}_40") (pintype "input"))
      (node (ref "IC2") (pin "42") (pinfunction "~{2RE}_42") (pintype "input"))
      (node (ref "IC2") (pin "5") (pinfunction "2DE_5") (pintype "input"))
      (node (ref "IC2") (pin "8") (pinfunction "3DE_8") (pintype "input"))
      (node (ref "R21") (pin "2") (pinfunction "2_2") (pintype "passive"))
      (node (ref "R23") (pin "1") (pinfunction "1_1") (pintype "passive"))
      (node (ref "T1") (pin "1") (pinfunction "G_1") (pintype "passive"))
      (node (ref "W1") (pin "1") (pinfunction "1_1") (pintype "bidirectional"))
    )
    (net (code "4") (name "/DIR_CTRL2") (class "Default")
      (node (ref "IC13") (pin "10") (pinfunction "P5_10") (pintype "bidirectional"))
      (node (ref "IC13") (pin "11") (pinfunction "P6_11") (pintype "bidirectional"))
      (node (ref "IC13") (pin "12") (pinfunction "P7_12") (pintype "bidirectional"))
      (node (ref "IC13") (pin "9") (pinfunction "P4_9") (pintype "bidirectional"))
      (node (ref "IC9") (pin "1") (pinfunction "1DE_1") (pintype "input"))
      (node (ref "IC9") (pin "12") (pinfunction "4DE_12") (pintype "input"))
      (node (ref "IC9") (pin "19") (pinfunction "~{3RE}_19") (pintype "input"))
      (node (ref "IC9") (pin "21") (pinfunction "~{4RE}_21") (pintype "input"))
      (node (ref "IC9") (pin "40") (pinfunction "~{1RE}_40") (pintype "input"))
      (node (ref "IC9") (pin "42") (pinfunction "~{2RE}_42") (pintype "input"))
      (node (ref "IC9") (pin "5") (pinfunction "2DE_5") (pintype "input"))
      (node (ref "IC9") (pin "8") (pinfunction "3DE_8") (pintype "input"))
      (node (ref "R24") (pin "2") (pinfunction "2_2") (pintype "passive"))
      (node (ref "R33") (pin "1") (pinfunction "1_1") (pintype "passive"))
      (node (ref "T3") (pin "1") (pinfunction "G_1") (pintype "passive"))
      (node (ref "W3") (pin "1") (pinfunction "1_1") (pintype "bidirectional"))
    )
    (net (code "5") (name "/I2C_SCL") (class "Default")
      (node (ref "IC13") (pin "14") (pinfunction "SCL_14") (pintype "input"))
      (node (ref "IC7") (pin "1") (pinfunction "SCL_1") (pintype "input"))
      (node (ref "J5") (pin "27") (pinfunction "27_27") (pintype "bidirectional"))
    )
    (net (code "6") (name "/I2C_SDA") (class "Default")
      (node (ref "IC13") (pin "15") (pinfunction "SDA_15") (pintype "bidirectional"))
      (node (ref "IC7") (pin "3") (pinfunction "SDA_3") (pintype "bidirectional"))
      (node (ref "J5") (pin "26") (pinfunction "26_26") (pintype "bidirectional"))
    )
    (net (code "7") (name "/IO1") (class "Default")
      (node (ref "IC1") (pin "22") (pinfunction "B2_22") (pintype "bidirectional"))
      (node (ref "IC1") (pin "23") (pinfunction "B1_23") (pintype "bidirectional"))
      (node (ref "J1") (pin "4") (pinfunction "4_4") (pintype "bidirectional"))
      (node (ref "R2") (pin "2") (pinfunction "2_2") (pintype "passive"))
    )
    (net (code "8") (name "/IO2") (class "Default")
      (node (ref "IC1") (pin "19") (pinfunction "B4_19") (pintype "bidirectional"))
      (node (ref "IC1") (pin "20") (pinfunction "B3_20") (pintype "bidirectional"))
      (node (ref "J2") (pin "4") (pinfunction "4_4") (pintype "bidirectional"))
      (node (ref "R4") (pin "2") (pinfunction "2_2") (pintype "passive"))
    )
    (net (code "9") (name "/IO3") (class "Default")
      (node (ref "IC1") (pin "17") (pinfunction "B6_17") (pintype "bidirectional"))
      (node (ref "IC1") (pin "18") (pinfunction "B5_18") (pintype "bidirectional"))
      (node (ref "J1") (pin "2") (pinfunction "2_2") (pintype "bidirectional"))
      (node (ref "R6") (pin "2") (pinfunction "2_2") (pintype "passive"))
    )
    (net (code "10") (name "/IO4") (class "Default")
      (node (ref "IC1") (pin "14") (pinfunction "B8_14") (pintype "bidirectional"))
      (node (ref "IC1") (pin "15") (pinfunction "B7_15") (pintype "bidirectional"))
      (node (ref "J2") (pin "2") (pinfunction "2_2") (pintype "bidirectional"))
      (node (ref "R8") (pin "2") (pinfunction "2_2") (pintype "passive"))
    )
    (net (code "11") (name "/IO5") (class "Default")
      (node (ref "IC8") (pin "22") (pinfunction "B2_22") (pintype "bidirectional"))
      (node (ref "IC8") (pin "23") (pinfunction "B1_23") (pintype "bidirectional"))
      (node (ref "J3") (pin "4") (pinfunction "4_4") (pintype "bidirectional"))
      (node (ref "R12") (pin "2") (pinfunction "2_2") (pintype "passive"))
    )
    (net (code "12") (name "/IO6") (class "Default")
      (node (ref "IC8") (pin "19") (pinfunction "B4_19") (pintype "bidirectional"))
      (node (ref "IC8") (pin "20") (pinfunction "B3_20") (pintype "bidirectional"))
      (node (ref "J4") (pin "4") (pinfunction "4_4") (pintype "bidirectional"))
      (node (ref "R14") (pin "2") (pinfunction "2_2") (pintype "passive"))
    )
    (net (code "13") (name "/IO7") (class "Default")
      (node (ref "IC8") (pin "17") (pinfunction "B6_17") (pintype "bidirectional"))
      (node (ref "IC8") (pin "18") (pinfunction "B5_18") (pintype "bidirectional"))
      (node (ref "J3") (pin "2") (pinfunction "2_2") (pintype "bidirectional"))
      (node (ref "R16") (pin "2") (pinfunction "2_2") (pintype "passive"))
    )
    (net (code "14") (name "/IO8") (class "Default")
      (node (ref "IC8") (pin "14") (pinfunction "B8_14") (pintype "bidirectional"))
      (node (ref "IC8") (pin "15") (pinfunction "B7_15") (pintype "bidirectional"))
      (node (ref "J4") (pin "2") (pinfunction "2_2") (pintype "bidirectional"))
      (node (ref "R18") (pin "2") (pinfunction "2_2") (pintype "passive"))
    )
    (net (code "15") (name "/LVDS1_N") (class "Default")
      (node (ref "IC2") (pin "48") (pinfunction "1B_48") (pintype "bidirectional"))
      (node (ref "J5") (pin "3") (pinfunction "3_3") (pintype "bidirectional"))
      (node (ref "R3") (pin "2") (pinfunction "2_2") (pintype "passive"))
    )
    (net (code "16") (name "/LVDS1_P") (class "Default")
      (node (ref "IC2") (pin "47") (pinfunction "1A_47") (pintype "bidirectional"))
      (node (ref "J5") (pin "2") (pinfunction "2_2") (pintype "bidirectional"))
      (node (ref "R3") (pin "1") (pinfunction "1_1") (pintype "passive"))
    )
    (net (code "17") (name "/LVDS2_N") (class "Default")
      (node (ref "IC2") (pin "4") (pinfunction "2B_4") (pintype "bidirectional"))
      (node (ref "J5") (pin "6") (pinfunction "6_6") (pintype "bidirectional"))
      (node (ref "R5") (pin "2") (pinfunction "2_2") (pintype "passive"))
    )
    (net (code "18") (name "/LVDS2_P") (class "Default")
      (node (ref "IC2") (pin "3") (pinfunction "2A_3") (pintype "bidirectional"))
      (node (ref "J5") (pin "5") (pinfunction "5_5") (pintype "bidirectional"))
      (node (ref "R5") (pin "1") (pinfunction "1_1") (pintype "passive"))
    )
    (net (code "19") (name "/LVDS3_N") (class "Default")
      (node (ref "IC2") (pin "10") (pinfunction "3B_10") (pintype "bidirectional"))
      (node (ref "J5") (pin "9") (pinfunction "9_9") (pintype "bidirectional"))
      (node (ref "R7") (pin "2") (pinfunction "2_2") (pintype "passive"))
    )
    (net (code "20") (name "/LVDS3_P") (class "Default")
      (node (ref "IC2") (pin "9") (pinfunction "3A_9") (pintype "bidirectional"))
      (node (ref "J5") (pin "8") (pinfunction "8_8") (pintype "bidirectional"))
      (node (ref "R7") (pin "1") (pinfunction "1_1") (pintype "passive"))
    )
    (net (code "21") (name "/LVDS4_N") (class "Default")
      (node (ref "IC2") (pin "14") (pinfunction "4B_14") (pintype "bidirectional"))
      (node (ref "J5") (pin "12") (pinfunction "12_12") (pintype "bidirectional"))
      (node (ref "R9") (pin "2") (pinfunction "2_2") (pintype "passive"))
    )
    (net (code "22") (name "/LVDS4_P") (class "Default")
      (node (ref "IC2") (pin "13") (pinfunction "4A_13") (pintype "bidirectional"))
      (node (ref "J5") (pin "11") (pinfunction "11_11") (pintype "bidirectional"))
      (node (ref "R9") (pin "1") (pinfunction "1_1") (pintype "passive"))
    )
    (net (code "23") (name "/LVDS5_N") (class "Default")
      (node (ref "IC9") (pin "48") (pinfunction "1B_48") (pintype "bidirectional"))
      (node (ref "J5") (pin "15") (pinfunction "15_15") (pintype "bidirectional"))
      (node (ref "R28") (pin "2") (pinfunction "2_2") (pintype "passive"))
    )
    (net (code "24") (name "/LVDS5_P") (class "Default")
      (node (ref "IC9") (pin "47") (pinfunction "1A_47") (pintype "bidirectional"))
      (node (ref "J5") (pin "14") (pinfunction "14_14") (pintype "bidirectional"))
      (node (ref "R28") (pin "1") (pinfunction "1_1") (pintype "passive"))
    )
    (net (code "25") (name "/LVDS6_N") (class "Default")
      (node (ref "IC9") (pin "4") (pinfunction "2B_4") (pintype "bidirectional"))
      (node (ref "J5") (pin "18") (pinfunction "18_18") (pintype "bidirectional"))
      (node (ref "R15") (pin "2") (pinfunction "2_2") (pintype "passive"))
    )
    (net (code "26") (name "/LVDS6_P") (class "Default")
      (node (ref "IC9") (pin "3") (pinfunction "2A_3") (pintype "bidirectional"))
      (node (ref "J5") (pin "17") (pinfunction "17_17") (pintype "bidirectional"))
      (node (ref "R15") (pin "1") (pinfunction "1_1") (pintype "passive"))
    )
    (net (code "27") (name "/LVDS7_N") (class "Default")
      (node (ref "IC9") (pin "10") (pinfunction "3B_10") (pintype "bidirectional"))
      (node (ref "J5") (pin "21") (pinfunction "21_21") (pintype "bidirectional"))
      (node (ref "R17") (pin "2") (pinfunction "2_2") (pintype "passive"))
    )
    (net (code "28") (name "/LVDS7_P") (class "Default")
      (node (ref "IC9") (pin "9") (pinfunction "3A_9") (pintype "bidirectional"))
      (node (ref "J5") (pin "20") (pinfunction "20_20") (pintype "bidirectional"))
      (node (ref "R17") (pin "1") (pinfunction "1_1") (pintype "passive"))
    )
    (net (code "29") (name "/LVDS8_N") (class "Default")
      (node (ref "IC9") (pin "14") (pinfunction "4B_14") (pintype "bidirectional"))
      (node (ref "J5") (pin "24") (pinfunction "24_24") (pintype "bidirectional"))
      (node (ref "R19") (pin "2") (pinfunction "2_2") (pintype "passive"))
    )
    (net (code "30") (name "/LVDS8_P") (class "Default")
      (node (ref "IC9") (pin "13") (pinfunction "4A_13") (pintype "bidirectional"))
      (node (ref "J5") (pin "23") (pinfunction "23_23") (pintype "bidirectional"))
      (node (ref "R19") (pin "1") (pinfunction "1_1") (pintype "passive"))
    )
    (net (code "31") (name "GND") (class "Default")
      (node (ref "C10") (pin "1") (pinfunction "1_1") (pintype "passive"))
      (node (ref "C11") (pin "1") (pinfunction "1_1") (pintype "passive"))
      (node (ref "C12") (pin "1") (pinfunction "1_1") (pintype "passive"))
      (node (ref "C13") (pin "1") (pinfunction "1_1") (pintype "passive"))
      (node (ref "C14") (pin "1") (pinfunction "1_1") (pintype "passive"))
      (node (ref "C15") (pin "1") (pinfunction "1_1") (pintype "passive"))
      (node (ref "C16") (pin "1") (pinfunction "1_1") (pintype "passive"))
      (node (ref "C17") (pin "1") (pinfunction "1_1") (pintype "passive"))
      (node (ref "C18") (pin "2") (pinfunction "2_2") (pintype "passive"))
      (node (ref "C19") (pin "1") (pinfunction "1_1") (pintype "passive"))
      (node (ref "C20") (pin "1") (pinfunction "1_1") (pintype "passive"))
      (node (ref "C21") (pin "1") (pinfunction "1_1") (pintype "passive"))
      (node (ref "C22") (pin "1") (pinfunction "1_1") (pintype "passive"))
      (node (ref "C23") (pin "1") (pinfunction "1_1") (pintype "passive"))
      (node (ref "C24") (pin "1") (pinfunction "1_1") (pintype "passive"))
      (node (ref "C25") (pin "1") (pinfunction "1_1") (pintype "passive"))
      (node (ref "C26") (pin "1") (pinfunction "1_1") (pintype "passive"))
      (node (ref "C27") (pin "2") (pinfunction "2_2") (pintype "passive"))
      (node (ref "C33") (pin "1") (pinfunction "1_1") (pintype "passive"))
      (node (ref "C34") (pin "2") (pinfunction "2_2") (pintype "passive"))
      (node (ref "C35") (pin "1") (pinfunction "1_1") (pintype "passive"))
      (node (ref "C36") (pin "2") (pinfunction "2_2") (pintype "passive"))
      (node (ref "C37") (pin "1") (pinfunction "1_1") (pintype "passive"))
      (node (ref "C38") (pin "1") (pinfunction "1_1") (pintype "passive"))
      (node (ref "C6") (pin "1") (pinfunction "1_1") (pintype "passive"))
      (node (ref "C7") (pin "1") (pinfunction "1_1") (pintype "passive"))
      (node (ref "C8") (pin "1") (pinfunction "1_1") (pintype "passive"))
      (node (ref "C9") (pin "1") (pinfunction "1_1") (pintype "passive"))
      (node (ref "IC10") (pin "9") (pinfunction "GND2_9") (pintype "power_in"))
      (node (ref "IC11") (pin "8") (pinfunction "GND1_8") (pintype "power_in"))
      (node (ref "IC12") (pin "2") (pinfunction "-Vin_2") (pintype "power_in"))
      (node (ref "IC13") (pin "1") (pinfunction "A0_1") (pintype "input"))
      (node (ref "IC13") (pin "8") (pinfunction "GND_8") (pintype "power_in"))
      (node (ref "IC2") (pin "18") (pinfunction "GND_18") (pintype "power_in"))
      (node (ref "IC2") (pin "23") (pinfunction "GND_23") (pintype "power_in"))
      (node (ref "IC2") (pin "27") (pinfunction "GND_27") (pintype "power_in"))
      (node (ref "IC2") (pin "31") (pinfunction "GND_31") (pintype "power_in"))
      (node (ref "IC2") (pin "34") (pinfunction "GND_34") (pintype "power_in"))
      (node (ref "IC2") (pin "38") (pinfunction "GND_38") (pintype "power_in"))
      (node (ref "IC2") (pin "43") (pinfunction "GND_43") (pintype "power_in"))
      (node (ref "IC2") (pin "49") (pinfunction "EP_49") (pintype "power_in"))
      (node (ref "IC2") (pin "6") (pinfunction "GND_6") (pintype "power_in"))
      (node (ref "IC2") (pin "7") (pinfunction "GND_7") (pintype "power_in"))
      (node (ref "IC3") (pin "9") (pinfunction "GND2_9") (pintype "power_in"))
      (node (ref "IC4") (pin "8") (pinfunction "GND1_8") (pintype "power_in"))
      (node (ref "IC5") (pin "1") (pinfunction "PGND_1") (pintype "power_in"))
      (node (ref "IC5") (pin "11") (pinfunction "EP_11") (pintype "power_in"))
      (node (ref "IC5") (pin "6") (pinfunction "AGND_6") (pintype "power_in"))
      (node (ref "IC6") (pin "2") (pinfunction "-Vin_2") (pintype "power_in"))
      (node (ref "IC7") (pin "2") (pinfunction "VSS_2") (pintype "power_in"))
      (node (ref "IC9") (pin "18") (pinfunction "GND_18") (pintype "power_in"))
      (node (ref "IC9") (pin "23") (pinfunction "GND_23") (pintype "power_in"))
      (node (ref "IC9") (pin "27") (pinfunction "GND_27") (pintype "power_in"))
      (node (ref "IC9") (pin "31") (pinfunction "GND_31") (pintype "power_in"))
      (node (ref "IC9") (pin "34") (pinfunction "GND_34") (pintype "power_in"))
      (node (ref "IC9") (pin "38") (pinfunction "GND_38") (pintype "power_in"))
      (node (ref "IC9") (pin "43") (pinfunction "GND_43") (pintype "power_in"))
      (node (ref "IC9") (pin "49") (pinfunction "EP_49") (pintype "power_in"))
      (node (ref "IC9") (pin "6") (pinfunction "GND_6") (pintype "power_in"))
      (node (ref "IC9") (pin "7") (pinfunction "GND_7") (pintype "power_in"))
      (node (ref "J5") (pin "1") (pinfunction "1_1") (pintype "bidirectional"))
      (node (ref "J5") (pin "10") (pinfunction "10_10") (pintype "bidirectional"))
      (node (ref "J5") (pin "13") (pinfunction "13_13") (pintype "bidirectional"))
      (node (ref "J5") (pin "16") (pinfunction "16_16") (pintype "bidirectional"))
      (node (ref "J5") (pin "19") (pinfunction "19_19") (pintype "bidirectional"))
      (node (ref "J5") (pin "22") (pinfunction "22_22") (pintype "bidirectional"))
      (node (ref "J5") (pin "25") (pinfunction "25_25") (pintype "bidirectional"))
      (node (ref "J5") (pin "4") (pinfunction "4_4") (pintype "bidirectional"))
      (node (ref "J5") (pin "7") (pinfunction "7_7") (pintype "bidirectional"))
      (node (ref "R10") (pin "2") (pinfunction "2_2") (pintype "passive"))
      (node (ref "R13") (pin "2") (pinfunction "2_2") (pintype "passive"))
      (node (ref "R20") (pin "2") (pinfunction "2_2") (pintype "passive"))
      (node (ref "R27") (pin "2") (pinfunction "2_2") (pintype "passive"))
      (node (ref "R30") (pin "1") (pinfunction "1_1") (pintype "passive"))
      (node (ref "T1") (pin "2") (pinfunction "S_2") (pintype "passive"))
      (node (ref "T3") (pin "2") (pinfunction "S_2") (pintype "passive"))
      (node (ref "W2") (pin "1") (pinfunction "1_1") (pintype "bidirectional"))
      (node (ref "W4") (pin "1") (pinfunction "1_1") (pintype "bidirectional"))
    )
    (net (code "32") (name "GND_ISO1") (class "Default")
      (node (ref "C1") (pin "1") (pinfunction "1_1") (pintype "passive"))
      (node (ref "C2") (pin "1") (pinfunction "1_1") (pintype "passive"))
      (node (ref "C3") (pin "1") (pinfunction "1_1") (pintype "passive"))
      (node (ref "C4") (pin "1") (pinfunction "1_1") (pintype "passive"))
      (node (ref "C5") (pin "2") (pinfunction "2_2") (pintype "passive"))
      (node (ref "IC1") (pin "11") (pinfunction "GND_11") (pintype "power_in"))
      (node (ref "IC1") (pin "2") (pinfunction "GND_2") (pintype "power_in"))
      (node (ref "IC1") (pin "5") (pinfunction "GND_5") (pintype "power_in"))
      (node (ref "IC1") (pin "8") (pinfunction "GND_8") (pintype "power_in"))
      (node (ref "IC3") (pin "8") (pinfunction "GND1_8") (pintype "power_in"))
      (node (ref "IC4") (pin "9") (pinfunction "GND2_9") (pintype "power_in"))
      (node (ref "IC6") (pin "4") (pinfunction "-Vout_4") (pintype "power_in"))
      (node (ref "J1") (pin "1") (pinfunction "1_1") (pintype "bidirectional"))
      (node (ref "J1") (pin "3") (pinfunction "3_3") (pintype "bidirectional"))
      (node (ref "J2") (pin "1") (pinfunction "1_1") (pintype "bidirectional"))
      (node (ref "J2") (pin "3") (pinfunction "3_3") (pintype "bidirectional"))
      (node (ref "R2") (pin "1") (pinfunction "1_1") (pintype "passive"))
      (node (ref "R4") (pin "1") (pinfunction "1_1") (pintype "passive"))
      (node (ref "R6") (pin "1") (pinfunction "1_1") (pintype "passive"))
      (node (ref "R8") (pin "1") (pinfunction "1_1") (pintype "passive"))
    )
    (net (code "33") (name "GND_ISO2") (class "Default")
      (node (ref "C28") (pin "1") (pinfunction "1_1") (pintype "passive"))
      (node (ref "C29") (pin "1") (pinfunction "1_1") (pintype "passive"))
      (node (ref "C30") (pin "1") (pinfunction "1_1") (pintype "passive"))
      (node (ref "C31") (pin "1") (pinfunction "1_1") (pintype "passive"))
      (node (ref "C32") (pin "2") (pinfunction "2_2") (pintype "passive"))
      (node (ref "IC10") (pin "8") (pinfunction "GND1_8") (pintype "power_in"))
      (node (ref "IC11") (pin "9") (pinfunction "GND2_9") (pintype "power_in"))
      (node (ref "IC12") (pin "4") (pinfunction "-Vout_4") (pintype "power_in"))
      (node (ref "IC8") (pin "11") (pinfunction "GND_11") (pintype "power_in"))
      (node (ref "IC8") (pin "2") (pinfunction "GND_2") (pintype "power_in"))
      (node (ref "IC8") (pin "5") (pinfunction "GND_5") (pintype "power_in"))
      (node (ref "IC8") (pin "8") (pinfunction "GND_8") (pintype "power_in"))
      (node (ref "J3") (pin "1") (pinfunction "1_1") (pintype "bidirectional"))
      (node (ref "J3") (pin "3") (pinfunction "3_3") (pintype "bidirectional"))
      (node (ref "J4") (pin "1") (pinfunction "1_1") (pintype "bidirectional"))
      (node (ref "J4") (pin "3") (pinfunction "3_3") (pintype "bidirectional"))
      (node (ref "R12") (pin "1") (pinfunction "1_1") (pintype "passive"))
      (node (ref "R14") (pin "1") (pinfunction "1_1") (pintype "passive"))
      (node (ref "R16") (pin "1") (pinfunction "1_1") (pintype "passive"))
      (node (ref "R18") (pin "1") (pinfunction "1_1") (pintype "passive"))
    )
    (net (code "34") (name "Net-(IC1-A1)") (class "Default")
      (node (ref "IC1") (pin "1") (pinfunction "A1_1") (pintype "bidirectional"))
      (node (ref "IC1") (pin "3") (pinfunction "A2_3") (pintype "bidirectional"))
      (node (ref "IC3") (pin "2") (pinfunction "A1_2") (pintype "input"))
      (node (ref "IC4") (pin "15") (pinfunction "B1_15") (pintype "output"))
    )
    (net (code "35") (name "Net-(IC1-A3)") (class "Default")
      (node (ref "IC1") (pin "4") (pinfunction "A3_4") (pintype "bidirectional"))
      (node (ref "IC1") (pin "6") (pinfunction "A4_6") (pintype "bidirectional"))
      (node (ref "IC3") (pin "3") (pinfunction "A2_3") (pintype "input"))
      (node (ref "IC4") (pin "14") (pinfunction "B2_14") (pintype "output"))
    )
    (net (code "36") (name "Net-(IC1-A5)") (class "Default")
      (node (ref "IC1") (pin "7") (pinfunction "A5_7") (pintype "bidirectional"))
      (node (ref "IC1") (pin "9") (pinfunction "A6_9") (pintype "bidirectional"))
      (node (ref "IC3") (pin "4") (pinfunction "A3_4") (pintype "input"))
      (node (ref "IC4") (pin "13") (pinfunction "B3_13") (pintype "output"))
    )
    (net (code "37") (name "Net-(IC1-A7)") (class "Default")
      (node (ref "IC1") (pin "10") (pinfunction "A7_10") (pintype "bidirectional"))
      (node (ref "IC1") (pin "12") (pinfunction "A8_12") (pintype "bidirectional"))
      (node (ref "IC3") (pin "5") (pinfunction "A4_5") (pintype "input"))
      (node (ref "IC4") (pin "12") (pinfunction "B4_12") (pintype "output"))
    )
    (net (code "38") (name "Net-(IC1-DIR)") (class "Default")
      (node (ref "IC1") (pin "24") (pinfunction "DIR_24") (pintype "input"))
      (node (ref "IC3") (pin "6") (pinfunction "A5_6") (pintype "output"))
      (node (ref "IC4") (pin "11") (pinfunction "B5_11") (pintype "input"))
    )
    (net (code "39") (name "Net-(IC2-1D)") (class "Default")
      (node (ref "IC2") (pin "35") (pinfunction "1D_35") (pintype "input"))
      (node (ref "IC3") (pin "15") (pinfunction "B1_15") (pintype "output"))
    )
    (net (code "40") (name "Net-(IC2-1FSEN)") (class "Default")
      (node (ref "IC2") (pin "20") (pinfunction "3FSEN_20") (pintype "input"))
      (node (ref "IC2") (pin "22") (pinfunction "4FSEN_22") (pintype "input"))
      (node (ref "IC2") (pin "39") (pinfunction "1FSEN_39") (pintype "input"))
      (node (ref "IC2") (pin "41") (pinfunction "2FSEN_41") (pintype "input"))
      (node (ref "R10") (pin "1") (pinfunction "1_1") (pintype "passive"))
      (node (ref "R13") (pin "1") (pinfunction "1_1") (pintype "passive"))
    )
    (net (code "41") (name "Net-(IC2-1R)") (class "Default")
      (node (ref "IC2") (pin "36") (pinfunction "1R_36") (pintype "output"))
      (node (ref "IC4") (pin "2") (pinfunction "A1_2") (pintype "input"))
    )
    (net (code "42") (name "Net-(IC2-2D)") (class "Default")
      (node (ref "IC2") (pin "32") (pinfunction "2D_32") (pintype "input"))
      (node (ref "IC3") (pin "14") (pinfunction "B2_14") (pintype "output"))
    )
    (net (code "43") (name "Net-(IC2-2R)") (class "Default")
      (node (ref "IC2") (pin "33") (pinfunction "2R_33") (pintype "output"))
      (node (ref "IC4") (pin "3") (pinfunction "A2_3") (pintype "input"))
    )
    (net (code "44") (name "Net-(IC2-3D)") (class "Default")
      (node (ref "IC2") (pin "28") (pinfunction "3D_28") (pintype "input"))
      (node (ref "IC3") (pin "13") (pinfunction "B3_13") (pintype "output"))
    )
    (net (code "45") (name "Net-(IC2-3R)") (class "Default")
      (node (ref "IC2") (pin "29") (pinfunction "3R_29") (pintype "output"))
      (node (ref "IC4") (pin "4") (pinfunction "A3_4") (pintype "input"))
    )
    (net (code "46") (name "Net-(IC2-4D)") (class "Default")
      (node (ref "IC2") (pin "25") (pinfunction "4D_25") (pintype "input"))
      (node (ref "IC3") (pin "12") (pinfunction "B4_12") (pintype "output"))
    )
    (net (code "47") (name "Net-(IC2-4R)") (class "Default")
      (node (ref "IC2") (pin "26") (pinfunction "4R_26") (pintype "output"))
      (node (ref "IC4") (pin "5") (pinfunction "A4_5") (pintype "input"))
    )
    (net (code "48") (name "Net-(IC3-B5)") (class "Default")
      (node (ref "IC3") (pin "11") (pinfunction "B5_11") (pintype "input"))
      (node (ref "R1") (pin "1") (pinfunction "1_1") (pintype "passive"))
      (node (ref "R22") (pin "2") (pinfunction "2_2") (pintype "passive"))
      (node (ref "T1") (pin "3") (pinfunction "D_3") (pintype "passive"))
    )
    (net (code "49") (name "Net-(IC5-FB)") (class "Default")
      (node (ref "IC5") (pin "5") (pinfunction "FB_5") (pintype "input"))
      (node (ref "R29") (pin "1") (pinfunction "1_1") (pintype "passive"))
      (node (ref "R30") (pin "2") (pinfunction "2_2") (pintype "passive"))
    )
    (net (code "50") (name "Net-(IC5-SW)") (class "Default")
      (node (ref "IC5") (pin "9") (pinfunction "SW_9") (pintype "output"))
      (node (ref "L1") (pin "1") (pinfunction "1_1") (pintype "passive"))
    )
    (net (code "51") (name "Net-(IC9-1FSEN)") (class "Default")
      (node (ref "IC9") (pin "20") (pinfunction "3FSEN_20") (pintype "input"))
      (node (ref "IC9") (pin "22") (pinfunction "4FSEN_22") (pintype "input"))
      (node (ref "IC9") (pin "39") (pinfunction "1FSEN_39") (pintype "input"))
      (node (ref "IC9") (pin "41") (pinfunction "2FSEN_41") (pintype "input"))
      (node (ref "R20") (pin "1") (pinfunction "1_1") (pintype "passive"))
      (node (ref "R27") (pin "1") (pinfunction "1_1") (pintype "passive"))
    )
    (net (code "52") (name "Net-(IC10-A1)") (class "Default")
      (node (ref "IC10") (pin "2") (pinfunction "A1_2") (pintype "input"))
      (node (ref "IC11") (pin "15") (pinfunction "B1_15") (pintype "output"))
      (node (ref "IC8") (pin "1") (pinfunction "A1_1") (pintype "bidirectional"))
      (node (ref "IC8") (pin "3") (pinfunction "A2_3") (pintype "bidirectional"))
    )
    (net (code "53") (name "Net-(IC10-A2)") (class "Default")
      (node (ref "IC10") (pin "3") (pinfunction "A2_3") (pintype "input"))
      (node (ref "IC11") (pin "14") (pinfunction "B2_14") (pintype "output"))
      (node (ref "IC8") (pin "4") (pinfunction "A3_4") (pintype "bidirectional"))
      (node (ref "IC8") (pin "6") (pinfunction "A4_6") (pintype "bidirectional"))
    )
    (net (code "54") (name "Net-(IC10-A3)") (class "Default")
      (node (ref "IC10") (pin "4") (pinfunction "A3_4") (pintype "input"))
      (node (ref "IC11") (pin "13") (pinfunction "B3_13") (pintype "output"))
      (node (ref "IC8") (pin "7") (pinfunction "A5_7") (pintype "bidirectional"))
      (node (ref "IC8") (pin "9") (pinfunction "A6_9") (pintype "bidirectional"))
    )
    (net (code "55") (name "Net-(IC10-A4)") (class "Default")
      (node (ref "IC10") (pin "5") (pinfunction "A4_5") (pintype "input"))
      (node (ref "IC11") (pin "12") (pinfunction "B4_12") (pintype "output"))
      (node (ref "IC8") (pin "10") (pinfunction "A7_10") (pintype "bidirectional"))
      (node (ref "IC8") (pin "12") (pinfunction "A8_12") (pintype "bidirectional"))
    )
    (net (code "56") (name "Net-(IC10-A5)") (class "Default")
      (node (ref "IC10") (pin "6") (pinfunction "A5_6") (pintype "output"))
      (node (ref "IC11") (pin "11") (pinfunction "B5_11") (pintype "input"))
      (node (ref "IC8") (pin "24") (pinfunction "DIR_24") (pintype "input"))
    )
    (net (code "57") (name "Net-(IC10-B1)") (class "Default")
      (node (ref "IC10") (pin "15") (pinfunction "B1_15") (pintype "output"))
      (node (ref "IC9") (pin "35") (pinfunction "1D_35") (pintype "input"))
    )
    (net (code "58") (name "Net-(IC10-B2)") (class "Default")
      (node (ref "IC10") (pin "14") (pinfunction "B2_14") (pintype "output"))
      (node (ref "IC9") (pin "32") (pinfunction "2D_32") (pintype "input"))
    )
    (net (code "59") (name "Net-(IC10-B3)") (class "Default")
      (node (ref "IC10") (pin "13") (pinfunction "B3_13") (pintype "output"))
      (node (ref "IC9") (pin "28") (pinfunction "3D_28") (pintype "input"))
    )
    (net (code "60") (name "Net-(IC10-B4)") (class "Default")
      (node (ref "IC10") (pin "12") (pinfunction "B4_12") (pintype "output"))
      (node (ref "IC9") (pin "25") (pinfunction "4D_25") (pintype "input"))
    )
    (net (code "61") (name "Net-(IC10-B5)") (class "Default")
      (node (ref "IC10") (pin "11") (pinfunction "B5_11") (pintype "input"))
      (node (ref "R11") (pin "1") (pinfunction "1_1") (pintype "passive"))
      (node (ref "R25") (pin "2") (pinfunction "2_2") (pintype "passive"))
      (node (ref "T3") (pin "3") (pinfunction "D_3") (pintype "passive"))
    )
    (net (code "62") (name "Net-(IC11-A1)") (class "Default")
      (node (ref "IC11") (pin "2") (pinfunction "A1_2") (pintype "input"))
      (node (ref "IC9") (pin "36") (pinfunction "1R_36") (pintype "output"))
    )
    (net (code "63") (name "Net-(IC11-A2)") (class "Default")
      (node (ref "IC11") (pin "3") (pinfunction "A2_3") (pintype "input"))
      (node (ref "IC9") (pin "33") (pinfunction "2R_33") (pintype "output"))
    )
    (net (code "64") (name "Net-(IC11-A3)") (class "Default")
      (node (ref "IC11") (pin "4") (pinfunction "A3_4") (pintype "input"))
      (node (ref "IC9") (pin "29") (pinfunction "3R_29") (pintype "output"))
    )
    (net (code "65") (name "Net-(IC11-A4)") (class "Default")
      (node (ref "IC11") (pin "5") (pinfunction "A4_5") (pintype "input"))
      (node (ref "IC9") (pin "26") (pinfunction "4R_26") (pintype "output"))
    )
    (net (code "66") (name "Net-(IC13-P0)") (class "Default")
      (node (ref "IC13") (pin "4") (pinfunction "P0_4") (pintype "bidirectional"))
      (node (ref "IC13") (pin "5") (pinfunction "P1_5") (pintype "bidirectional"))
      (node (ref "IC13") (pin "6") (pinfunction "P2_6") (pintype "bidirectional"))
      (node (ref "IC13") (pin "7") (pinfunction "P3_7") (pintype "bidirectional"))
    )
    (net (code "67") (name "Net-(LD1-C)") (class "Default")
      (node (ref "LD1") (pin "1") (pinfunction "C_1") (pintype "passive"))
      (node (ref "R21") (pin "1") (pinfunction "1_1") (pintype "passive"))
    )
    (net (code "68") (name "Net-(LD2-C)") (class "Default")
      (node (ref "LD2") (pin "1") (pinfunction "C_1") (pintype "passive"))
      (node (ref "R22") (pin "1") (pinfunction "1_1") (pintype "passive"))
    )
    (net (code "69") (name "Net-(LD3-C)") (class "Default")
      (node (ref "LD3") (pin "1") (pinfunction "C_1") (pintype "passive"))
      (node (ref "R24") (pin "1") (pinfunction "1_1") (pintype "passive"))
    )
    (net (code "70") (name "Net-(LD4-C)") (class "Default")
      (node (ref "LD4") (pin "1") (pinfunction "C_1") (pintype "passive"))
      (node (ref "R25") (pin "1") (pinfunction "1_1") (pintype "passive"))
    )
    (net (code "71") (name "P3V3") (class "Default")
      (node (ref "C10") (pin "2") (pinfunction "2_2") (pintype "passive"))
      (node (ref "C11") (pin "2") (pinfunction "2_2") (pintype "passive"))
      (node (ref "C12") (pin "2") (pinfunction "2_2") (pintype "passive"))
      (node (ref "C13") (pin "2") (pinfunction "2_2") (pintype "passive"))
      (node (ref "C14") (pin "2") (pinfunction "2_2") (pintype "passive"))
      (node (ref "C15") (pin "2") (pinfunction "2_2") (pintype "passive"))
      (node (ref "C16") (pin "2") (pinfunction "2_2") (pintype "passive"))
      (node (ref "C17") (pin "2") (pinfunction "2_2") (pintype "passive"))
      (node (ref "C18") (pin "1") (pinfunction "1_1") (pintype "passive"))
      (node (ref "C19") (pin "2") (pinfunction "2_2") (pintype "passive"))
      (node (ref "C20") (pin "2") (pinfunction "2_2") (pintype "passive"))
      (node (ref "C21") (pin "2") (pinfunction "2_2") (pintype "passive"))
      (node (ref "C22") (pin "2") (pinfunction "2_2") (pintype "passive"))
      (node (ref "C23") (pin "2") (pinfunction "2_2") (pintype "passive"))
      (node (ref "C24") (pin "2") (pinfunction "2_2") (pintype "passive"))
      (node (ref "C25") (pin "2") (pinfunction "2_2") (pintype "passive"))
      (node (ref "C26") (pin "2") (pinfunction "2_2") (pintype "passive"))
      (node (ref "C27") (pin "1") (pinfunction "1_1") (pintype "passive"))
      (node (ref "C7") (pin "2") (pinfunction "2_2") (pintype "passive"))
      (node (ref "C8") (pin "2") (pinfunction "2_2") (pintype "passive"))
      (node (ref "IC10") (pin "10") (pinfunction "EN2_10") (pintype "input"))
      (node (ref "IC10") (pin "16") (pinfunction "VDD2_16") (pintype "power_in"))
      (node (ref "IC11") (pin "1") (pinfunction "VDD1_1") (pintype "power_in"))
      (node (ref "IC11") (pin "7") (pinfunction "EN1_7") (pintype "input"))
      (node (ref "IC2") (pin "11") (pinfunction "VCC_11") (pintype "power_in"))
      (node (ref "IC2") (pin "15") (pinfunction "VCC_15") (pintype "power_in"))
      (node (ref "IC2") (pin "16") (pinfunction "VCC_16") (pintype "power_in"))
      (node (ref "IC2") (pin "2") (pinfunction "VCC_2") (pintype "power_in"))
      (node (ref "IC2") (pin "24") (pinfunction "VCC_24") (pintype "power_in"))
      (node (ref "IC2") (pin "30") (pinfunction "PDN_30") (pintype "input"))
      (node (ref "IC2") (pin "37") (pinfunction "VCC_37") (pintype "power_in"))
      (node (ref "IC2") (pin "45") (pinfunction "VCC_45") (pintype "power_in"))
      (node (ref "IC2") (pin "46") (pinfunction "VCC_46") (pintype "power_in"))
      (node (ref "IC3") (pin "10") (pinfunction "EN2_10") (pintype "input"))
      (node (ref "IC3") (pin "16") (pinfunction "VDD2_16") (pintype "power_in"))
      (node (ref "IC4") (pin "1") (pinfunction "VDD1_1") (pintype "power_in"))
      (node (ref "IC4") (pin "7") (pinfunction "EN1_7") (pintype "input"))
      (node (ref "IC5") (pin "10") (pinfunction "VOS_10") (pintype "input"))
      (node (ref "IC5") (pin "8") (pinfunction "SLEEP_8") (pintype "input"))
      (node (ref "IC9") (pin "11") (pinfunction "VCC_11") (pintype "power_in"))
      (node (ref "IC9") (pin "15") (pinfunction "VCC_15") (pintype "power_in"))
      (node (ref "IC9") (pin "16") (pinfunction "VCC_16") (pintype "power_in"))
      (node (ref "IC9") (pin "2") (pinfunction "VCC_2") (pintype "power_in"))
      (node (ref "IC9") (pin "24") (pinfunction "VCC_24") (pintype "power_in"))
      (node (ref "IC9") (pin "30") (pinfunction "PDN_30") (pintype "input"))
      (node (ref "IC9") (pin "37") (pinfunction "VCC_37") (pintype "power_in"))
      (node (ref "IC9") (pin "45") (pinfunction "VCC_45") (pintype "power_in"))
      (node (ref "IC9") (pin "46") (pinfunction "VCC_46") (pintype "power_in"))
      (node (ref "L1") (pin "2") (pinfunction "2_2") (pintype "passive"))
      (node (ref "LD1") (pin "2") (pinfunction "A_2") (pintype "passive"))
      (node (ref "LD2") (pin "2") (pinfunction "A_2") (pintype "passive"))
      (node (ref "LD3") (pin "2") (pinfunction "A_2") (pintype "passive"))
      (node (ref "LD4") (pin "2") (pinfunction "A_2") (pintype "passive"))
      (node (ref "R1") (pin "2") (pinfunction "2_2") (pintype "passive"))
      (node (ref "R11") (pin "2") (pinfunction "2_2") (pintype "passive"))
      (node (ref "R23") (pin "2") (pinfunction "2_2") (pintype "passive"))
      (node (ref "R29") (pin "2") (pinfunction "2_2") (pintype "passive"))
      (node (ref "R33") (pin "2") (pinfunction "2_2") (pintype "passive"))
    )
    (net (code "72") (name "P3V3_MP") (class "Default")
      (node (ref "C37") (pin "2") (pinfunction "2_2") (pintype "passive"))
      (node (ref "C38") (pin "2") (pinfunction "2_2") (pintype "passive"))
      (node (ref "IC13") (pin "16") (pinfunction "VCC_16") (pintype "bidirectional"))
      (node (ref "IC13") (pin "2") (pinfunction "A1_2") (pintype "input"))
      (node (ref "IC13") (pin "3") (pinfunction "A2_3") (pintype "input"))
      (node (ref "IC7") (pin "4") (pinfunction "VCC_4") (pintype "power_in"))
      (node (ref "J5") (pin "30") (pinfunction "30_30") (pintype "bidirectional"))
    )
    (net (code "73") (name "P5V0_ISO1") (class "Default")
      (node (ref "C1") (pin "2") (pinfunction "2_2") (pintype "passive"))
      (node (ref "C2") (pin "2") (pinfunction "2_2") (pintype "passive"))
      (node (ref "C3") (pin "2") (pinfunction "2_2") (pintype "passive"))
      (node (ref "C4") (pin "2") (pinfunction "2_2") (pintype "passive"))
      (node (ref "C5") (pin "1") (pinfunction "1_1") (pintype "passive"))
      (node (ref "IC1") (pin "13") (pinfunction "OE_13") (pintype "input"))
      (node (ref "IC1") (pin "16") (pinfunction "VCC_16") (pintype "power_in"))
      (node (ref "IC1") (pin "21") (pinfunction "VCC_21") (pintype "power_in"))
      (node (ref "IC3") (pin "1") (pinfunction "VDD1_1") (pintype "power_in"))
      (node (ref "IC3") (pin "7") (pinfunction "EN1_7") (pintype "input"))
      (node (ref "IC4") (pin "10") (pinfunction "EN2_10") (pintype "input"))
      (node (ref "IC4") (pin "16") (pinfunction "VDD2_16") (pintype "power_in"))
      (node (ref "IC6") (pin "6") (pinfunction "+Vout_6") (pintype "power_in"))
    )
    (net (code "74") (name "P5V0_ISO2") (class "Default")
      (node (ref "C28") (pin "2") (pinfunction "2_2") (pintype "passive"))
      (node (ref "C29") (pin "2") (pinfunction "2_2") (pintype "passive"))
      (node (ref "C30") (pin "2") (pinfunction "2_2") (pintype "passive"))
      (node (ref "C31") (pin "2") (pinfunction "2_2") (pintype "passive"))
      (node (ref "C32") (pin "1") (pinfunction "1_1") (pintype "passive"))
      (node (ref "IC10") (pin "1") (pinfunction "VDD1_1") (pintype "power_in"))
      (node (ref "IC10") (pin "7") (pinfunction "EN1_7") (pintype "input"))
      (node (ref "IC11") (pin "10") (pinfunction "EN2_10") (pintype "input"))
      (node (ref "IC11") (pin "16") (pinfunction "VDD2_16") (pintype "power_in"))
      (node (ref "IC12") (pin "6") (pinfunction "+Vout_6") (pintype "power_in"))
      (node (ref "IC8") (pin "13") (pinfunction "OE_13") (pintype "input"))
      (node (ref "IC8") (pin "16") (pinfunction "VCC_16") (pintype "power_in"))
      (node (ref "IC8") (pin "21") (pinfunction "VCC_21") (pintype "power_in"))
    )
    (net (code "75") (name "P12V0") (class "Default")
      (node (ref "C33") (pin "2") (pinfunction "2_2") (pintype "passive"))
      (node (ref "C34") (pin "1") (pinfunction "1_1") (pintype "passive"))
      (node (ref "C35") (pin "2") (pinfunction "2_2") (pintype "passive"))
      (node (ref "C36") (pin "1") (pinfunction "1_1") (pintype "passive"))
      (node (ref "C6") (pin "2") (pinfunction "2_2") (pintype "passive"))
      (node (ref "C9") (pin "2") (pinfunction "2_2") (pintype "passive"))
      (node (ref "IC12") (pin "1") (pinfunction "+Vin_1") (pintype "power_in"))
      (node (ref "IC5") (pin "2") (pinfunction "VIN_2") (pintype "input"))
      (node (ref "IC5") (pin "3") (pinfunction "EN_3") (pintype "input"))
      (node (ref "IC6") (pin "1") (pinfunction "+Vin_1") (pintype "power_in"))
      (node (ref "J5") (pin "28") (pinfunction "28_28") (pintype "bidirectional"))
      (node (ref "J5") (pin "29") (pinfunction "29_29") (pintype "bidirectional"))
    )
    (net (code "76") (name "unconnected-(IC2-NC-Pad17)") (class "Default")
      (node (ref "IC2") (pin "17") (pinfunction "NC_17") (pintype "passive"))
    )
    (net (code "77") (name "unconnected-(IC2-NC-Pad44)") (class "Default")
      (node (ref "IC2") (pin "44") (pinfunction "NC_44") (pintype "passive"))
    )
    (net (code "78") (name "unconnected-(IC5-NC-Pad4)") (class "Default")
      (node (ref "IC5") (pin "4") (pinfunction "NC_4") (pintype "passive"))
    )
    (net (code "79") (name "unconnected-(IC5-PG-Pad7)") (class "Default")
      (node (ref "IC5") (pin "7") (pinfunction "PG_7") (pintype "output"))
    )
    (net (code "80") (name "unconnected-(IC7-NC-Pad5)") (class "Default")
      (node (ref "IC7") (pin "5") (pinfunction "NC_5") (pintype "passive"))
    )
    (net (code "81") (name "unconnected-(IC9-NC-Pad17)") (class "Default")
      (node (ref "IC9") (pin "17") (pinfunction "NC_17") (pintype "passive"))
    )
    (net (code "82") (name "unconnected-(IC9-NC-Pad44)") (class "Default")
      (node (ref "IC9") (pin "44") (pinfunction "NC_44") (pintype "passive"))
    )
    (net (code "83") (name "unconnected-(IC13-~{INT}-Pad13)") (class "Default")
      (node (ref "IC13") (pin "13") (pinfunction "~{INT}_13") (pintype "output"))
    )
    (net (code "84") (name "unconnected-(SW1-Pad1)") (class "Default")
      (node (ref "SW1") (pin "1") (pinfunction "1_1") (pintype "bidirectional"))
    )
    (net (code "85") (name "unconnected-(SW2-Pad1)") (class "Default")
      (node (ref "SW2") (pin "1") (pinfunction "1_1") (pintype "bidirectional"))
    )
  )
)
